# Power.net
KiCad netlist of a schematic drawn in Altium Designer
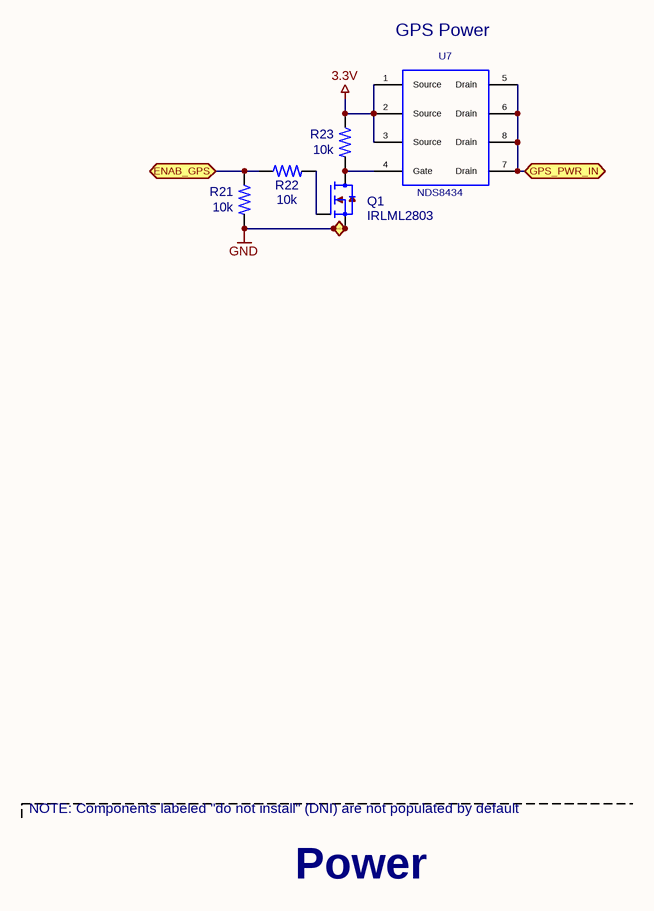
[diagram p0: Power.SchDoc]

(export (version "E")
  (design (tool "Eeschema 10.0.6"))
  (components
    (comp (ref "Q1")
      (value "IRLML2803")
      (footprint "SOT-23")
      (libsource (lib "mainboard_1") (part "IRLML2803TRPBF"))
    )
    (comp (ref "R21")
      (value "10k")
      (footprint "R_0603_1608Metric")
      (fields (field (name "MPN") "RNCP0603FTD10K0"))
      (libsource (lib "mainboard_1") (part "R-US_R0603"))
    )
    (comp (ref "R22")
      (value "10k")
      (footprint "R_0603_1608Metric")
      (fields (field (name "MPN") "RNCP0603FTD10K0"))
      (libsource (lib "mainboard_1") (part "R-US_R0603"))
    )
    (comp (ref "R23")
      (value "10k")
      (footprint "R_0603_1608Metric")
      (fields (field (name "MPN") "RNCP0603FTD10K0"))
      (libsource (lib "mainboard_1") (part "R-US_R0603"))
    )
    (comp (ref "U7")
      (value "NDS8434")
      (footprint "NDS8434")
      (fields (field (name "MPN") "IRF7404TRPBF"))
      (libsource (lib "mainboard_1") (part "NDS8434"))
    )
  )
  (nets
    (net (code "1") (name "/ENAB_GPS") (class "Default")
      (node (ref "R21") (pin "1") (pinfunction "1_1") (pintype "passive"))
      (node (ref "R22") (pin "1") (pinfunction "1_1") (pintype "passive"))
    )
    (net (code "2") (name "/GPS_PWR_IN") (class "Default")
      (node (ref "U7") (pin "5") (pinfunction "Drain_5") (pintype "passive"))
      (node (ref "U7") (pin "6") (pinfunction "Drain_6") (pintype "passive"))
      (node (ref "U7") (pin "7") (pinfunction "Drain_7") (pintype "passive"))
      (node (ref "U7") (pin "8") (pinfunction "Drain_8") (pintype "passive"))
    )
    (net (code "3") (name "3.3V") (class "Default")
      (node (ref "R23") (pin "1") (pinfunction "1_1") (pintype "passive"))
      (node (ref "U7") (pin "1") (pinfunction "Source_1") (pintype "passive"))
      (node (ref "U7") (pin "2") (pinfunction "Source_2") (pintype "passive"))
      (node (ref "U7") (pin "3") (pinfunction "Source_3") (pintype "passive"))
    )
    (net (code "4") (name "GND") (class "Default")
      (node (ref "Q1") (pin "2") (pinfunction "S_2") (pintype "passive"))
      (node (ref "R21") (pin "2") (pinfunction "2_2") (pintype "passive"))
    )
    (net (code "5") (name "Net-(Q1-D)") (class "Default")
      (node (ref "Q1") (pin "3") (pinfunction "D_3") (pintype "passive"))
      (node (ref "R23") (pin "2") (pinfunction "2_2") (pintype "passive"))
      (node (ref "U7") (pin "4") (pinfunction "Gate_4") (pintype "passive"))
    )
    (net (code "6") (name "Net-(Q1-G)") (class "Default")
      (node (ref "Q1") (pin "1") (pinfunction "G_1") (pintype "passive"))
      (node (ref "R22") (pin "2") (pinfunction "2_2") (pintype "passive"))
    )
  )
)
